# 03_UI_Outputs.net
KiCad netlist of a schematic drawn in Altium Designer
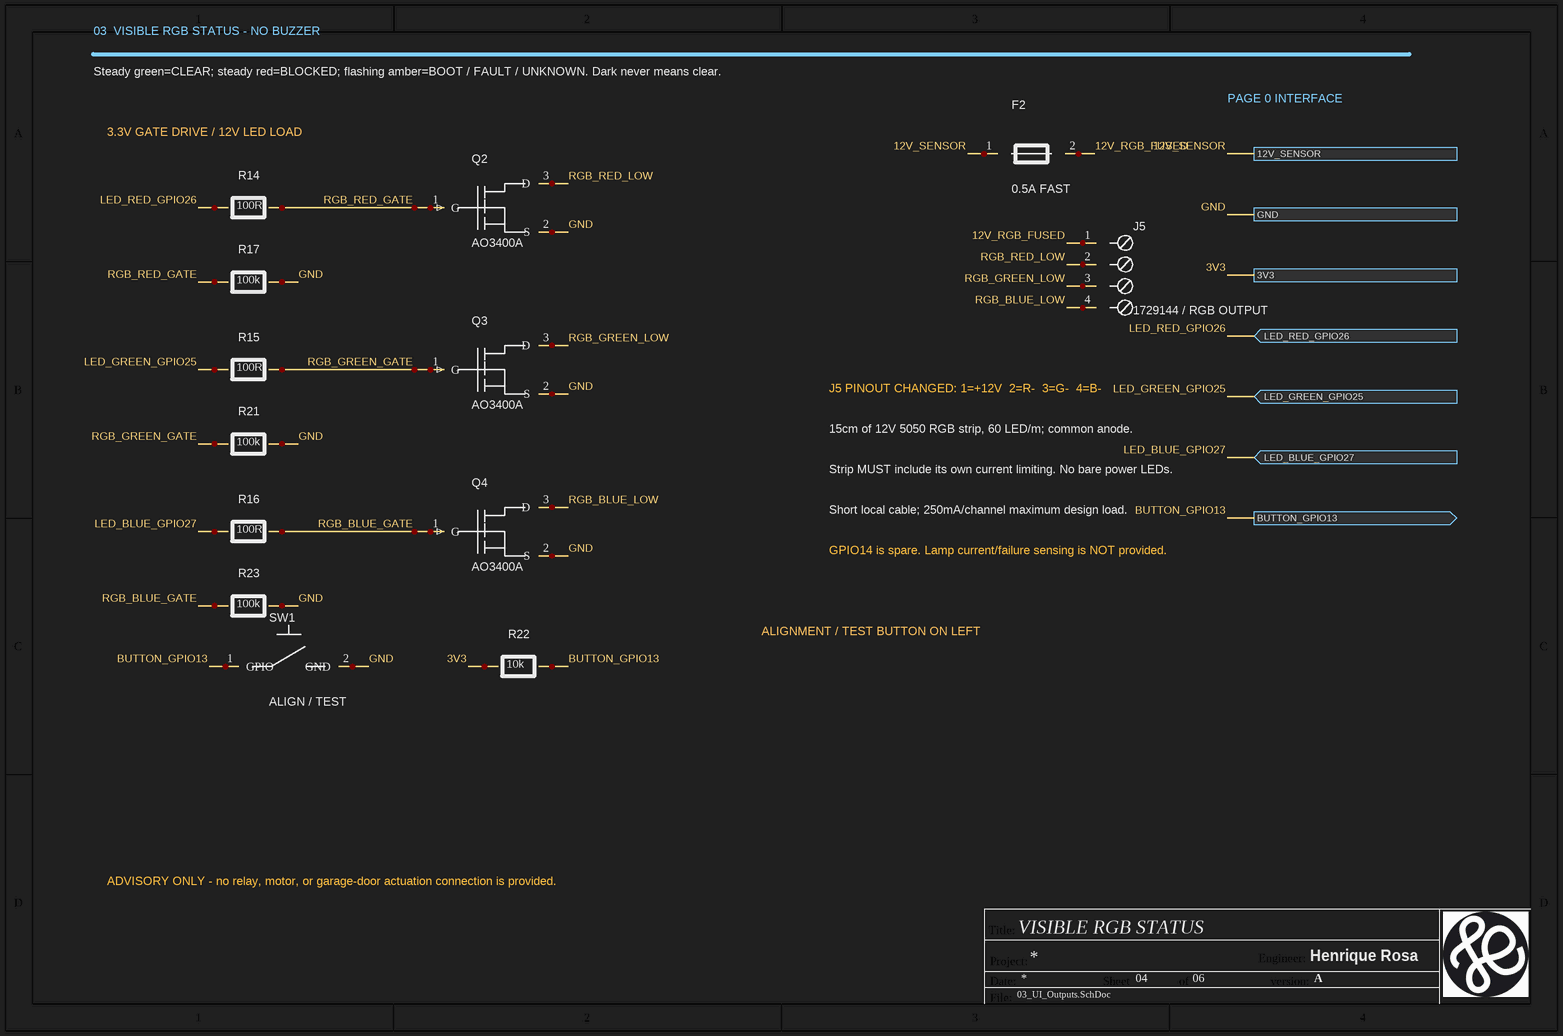
[diagram p0: 03_UI_Outputs.SchDoc]

(export (version "E")
  (design (tool "Eeschema 10.0.6"))
  (components
    (comp (ref "F2")
      (value "0.5A FAST")
      (footprint "PinRepairFootprints:LITTELFUSE_0451_2410")
      (description "RGB cable branch fuse; verify fault clearing with selected supply")
      (fields
        (field (name "MANUFACTURER") "Littelfuse")
        (field (name "MANUFACTURER PART NUMBER") "0451.500MRL")
      )
      (libsource (lib "*") (part "0451.500MRL"))
    )
    (comp (ref "J5")
      (value "1729144 / RGB OUTPUT")
      (footprint "PartSpecificFootprints:PHOENIX_1729144_MKDSN_4_508")
      (description "Common-anode analogue RGB strip; NOT addressable")
      (fields
        (field (name "MANUFACTURER") "Phoenix Contact")
        (field (name "MANUFACTURER PART NUMBER") "1729144")
      )
      (libsource (lib "PartSpecificComponents") (part "PHOENIX_1729144"))
    )
    (comp (ref "Q2")
      (value "AO3400A")
      (footprint "PinRepairFootprints:AO3400A_G1_S2_D3")
      (description "30V NMOS; Rds(on) specified at Vgs=2.5V; limit load to 250mA/channel")
      (fields (field (name "MANUFACTURER") "Alpha and Omega Semiconductor"))
      (libsource (lib "*") (part "AO3400A"))
    )
    (comp (ref "Q3")
      (value "AO3400A")
      (footprint "PinRepairFootprints:AO3400A_G1_S2_D3")
      (description "30V NMOS; Rds(on) specified at Vgs=2.5V; limit load to 250mA/channel")
      (fields (field (name "MANUFACTURER") "Alpha and Omega Semiconductor"))
      (libsource (lib "*") (part "AO3400A"))
    )
    (comp (ref "Q4")
      (value "AO3400A")
      (footprint "PinRepairFootprints:AO3400A_G1_S2_D3")
      (description "30V NMOS; Rds(on) specified at Vgs=2.5V; limit load to 250mA/channel")
      (fields (field (name "MANUFACTURER") "Alpha and Omega Semiconductor"))
      (libsource (lib "*") (part "AO3400A"))
    )
    (comp (ref "R14")
      (value "100R")
      (footprint "PCB - RESISTOR - CHIP - YAGEO RES 0805_2012:YAGEO RES 0805_2012")
      (description "MOSFET gate series resistor")
      (fields
        (field (name "MANUFACTURER") "Yageo")
        (field (name "MANUFACTURER PART NUMBER") "RC0805FR-07100RL")
      )
      (libsource (lib "Miscellaneous Devices") (part "RC0805FR-07100RL"))
    )
    (comp (ref "R15")
      (value "100R")
      (footprint "PCB - RESISTOR - CHIP - YAGEO RES 0805_2012:YAGEO RES 0805_2012")
      (description "MOSFET gate series resistor")
      (fields
        (field (name "MANUFACTURER") "Yageo")
        (field (name "MANUFACTURER PART NUMBER") "RC0805FR-07100RL")
      )
      (libsource (lib "Miscellaneous Devices") (part "RC0805FR-07100RL"))
    )
    (comp (ref "R16")
      (value "100R")
      (footprint "PCB - RESISTOR - CHIP - YAGEO RES 0805_2012:YAGEO RES 0805_2012")
      (description "MOSFET gate series resistor")
      (fields
        (field (name "MANUFACTURER") "Yageo")
        (field (name "MANUFACTURER PART NUMBER") "RC0805FR-07100RL")
      )
      (libsource (lib "Miscellaneous Devices") (part "RC0805FR-07100RL"))
    )
    (comp (ref "R17")
      (value "100k")
      (footprint "PCB - RESISTOR - CHIP - YAGEO RES 0805_2012:YAGEO RES 0805_2012")
      (description "Gate-source pull-down; off while ESP32 resets")
      (fields
        (field (name "MANUFACTURER") "Yageo")
        (field (name "MANUFACTURER PART NUMBER") "RC0805FR-07100KL")
      )
      (libsource (lib "Miscellaneous Devices") (part "RC0805FR-07100KL"))
    )
    (comp (ref "R21")
      (value "100k")
      (footprint "PCB - RESISTOR - CHIP - YAGEO RES 0805_2012:YAGEO RES 0805_2012")
      (description "Gate-source pull-down; off while ESP32 resets")
      (fields
        (field (name "MANUFACTURER") "Yageo")
        (field (name "MANUFACTURER PART NUMBER") "RC0805FR-07100KL")
      )
      (libsource (lib "Miscellaneous Devices") (part "RC0805FR-07100KL"))
    )
    (comp (ref "R22")
      (value "10k")
      (footprint "PCB - RESISTOR - CHIP - YAGEO RES 0805_2012:YAGEO RES 0805_2012")
      (description "Test button external pull-up")
      (fields
        (field (name "MANUFACTURER") "Yageo")
        (field (name "MANUFACTURER PART NUMBER") "RC0805FR-0710KL")
      )
      (libsource (lib "Miscellaneous Devices") (part "RC0805FR-0710KL"))
    )
    (comp (ref "R23")
      (value "100k")
      (footprint "PCB - RESISTOR - CHIP - YAGEO RES 0805_2012:YAGEO RES 0805_2012")
      (description "Gate-source pull-down; off while ESP32 resets")
      (fields
        (field (name "MANUFACTURER") "Yageo")
        (field (name "MANUFACTURER PART NUMBER") "RC0805FR-07100KL")
      )
      (libsource (lib "Miscellaneous Devices") (part "RC0805FR-07100KL"))
    )
    (comp (ref "SW1")
      (value "ALIGN / TEST")
      (footprint "PinRepairFootprints:OMRON_B3FS1000P_LOGICAL_1_2")
      (description "Momentary test switch")
      (fields (field (name "MANUFACTURER") "Omron") (field (name "MANUFACTURER PART NUMBER") "B3FS-1000P"))
      (libsource (lib "*") (part "B3FS-1000P"))
    )
  )
  (nets
    (net (code "1") (name "/3V3") (class "Default")
      (node (ref "R22") (pin "1") (pinfunction "1_1") (pintype "passive"))
    )
    (net (code "2") (name "/12V_RGB_FUSED") (class "Default")
      (node (ref "F2") (pin "2") (pintype "passive"))
      (node (ref "J5") (pin "1") (pinfunction "+12V_1") (pintype "power_in"))
    )
    (net (code "3") (name "/12V_SENSOR") (class "Default") (node (ref "F2") (pin "1") (pintype "passive")))
    (net (code "4") (name "/BUTTON_GPIO13") (class "Default")
      (node (ref "R22") (pin "2") (pinfunction "2_2") (pintype "passive"))
      (node (ref "SW1") (pin "1") (pinfunction "GPIO_1") (pintype "passive"))
    )
    (net (code "5") (name "/GND") (class "Default")
      (node (ref "Q2") (pin "2") (pinfunction "S_2") (pintype "passive"))
      (node (ref "Q3") (pin "2") (pinfunction "S_2") (pintype "passive"))
      (node (ref "Q4") (pin "2") (pinfunction "S_2") (pintype "passive"))
      (node (ref "R17") (pin "2") (pinfunction "2_2") (pintype "passive"))
      (node (ref "R21") (pin "2") (pinfunction "2_2") (pintype "passive"))
      (node (ref "R23") (pin "2") (pinfunction "2_2") (pintype "passive"))
      (node (ref "SW1") (pin "2") (pinfunction "GND_2") (pintype "passive"))
    )
    (net (code "6") (name "/LED_BLUE_GPIO27") (class "Default")
      (node (ref "R16") (pin "1") (pinfunction "1_1") (pintype "passive"))
    )
    (net (code "7") (name "/LED_GREEN_GPIO25") (class "Default")
      (node (ref "R15") (pin "1") (pinfunction "1_1") (pintype "passive"))
    )
    (net (code "8") (name "/LED_RED_GPIO26") (class "Default")
      (node (ref "R14") (pin "1") (pinfunction "1_1") (pintype "passive"))
    )
    (net (code "9") (name "/RGB_BLUE_GATE") (class "Default")
      (node (ref "Q4") (pin "1") (pinfunction "G_1") (pintype "input"))
      (node (ref "R16") (pin "2") (pinfunction "2_2") (pintype "passive"))
      (node (ref "R23") (pin "1") (pinfunction "1_1") (pintype "passive"))
    )
    (net (code "10") (name "/RGB_BLUE_LOW") (class "Default")
      (node (ref "J5") (pin "4") (pinfunction "B-_4") (pintype "passive"))
      (node (ref "Q4") (pin "3") (pinfunction "D_3") (pintype "passive"))
    )
    (net (code "11") (name "/RGB_GREEN_GATE") (class "Default")
      (node (ref "Q3") (pin "1") (pinfunction "G_1") (pintype "input"))
      (node (ref "R15") (pin "2") (pinfunction "2_2") (pintype "passive"))
      (node (ref "R21") (pin "1") (pinfunction "1_1") (pintype "passive"))
    )
    (net (code "12") (name "/RGB_GREEN_LOW") (class "Default")
      (node (ref "J5") (pin "3") (pinfunction "G-_3") (pintype "passive"))
      (node (ref "Q3") (pin "3") (pinfunction "D_3") (pintype "passive"))
    )
    (net (code "13") (name "/RGB_RED_GATE") (class "Default")
      (node (ref "Q2") (pin "1") (pinfunction "G_1") (pintype "input"))
      (node (ref "R14") (pin "2") (pinfunction "2_2") (pintype "passive"))
      (node (ref "R17") (pin "1") (pinfunction "1_1") (pintype "passive"))
    )
    (net (code "14") (name "/RGB_RED_LOW") (class "Default")
      (node (ref "J5") (pin "2") (pinfunction "R-_2") (pintype "passive"))
      (node (ref "Q2") (pin "3") (pinfunction "D_3") (pintype "passive"))
    )
  )
)
